# canDrive_hw_board2_v2.net
KiCad netlist of a schematic drawn in Altium Designer
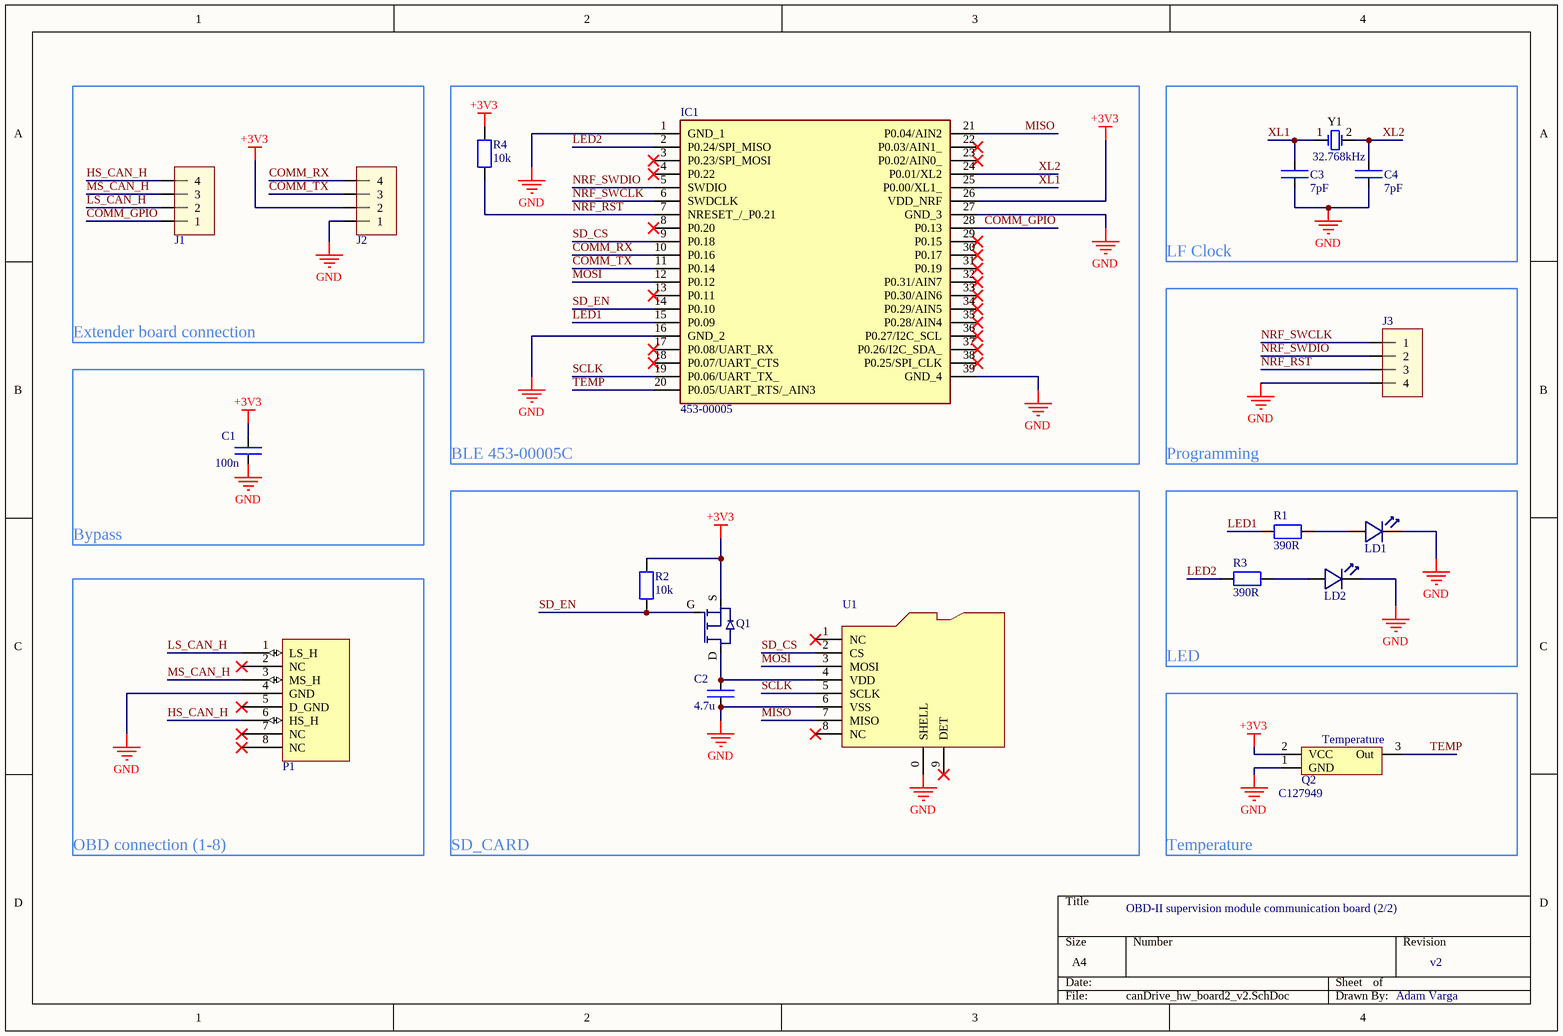
[diagram p0: canDrive_hw_board2_v2.SchDoc]

(export (version "E")
  (design (tool "Eeschema 10.0.6"))
  (components
    (comp (ref "C1")
      (value "100n")
      (footprint "C0603")
      (description "Capacitor")
      (libsource (lib "canDrive_comp_sch_lib") (part "Capacitor"))
    )
    (comp (ref "C2")
      (value "4.7u")
      (footprint "C0603")
      (description "Capacitor")
      (libsource (lib "canDrive_comp_sch_lib") (part "Capacitor"))
    )
    (comp (ref "C3")
      (value "7pF")
      (footprint "C0603")
      (description "Capacitor")
      (fields (field (name "PART") "C326971"))
      (libsource (lib "canDrive_comp_sch_lib") (part "Capacitor"))
    )
    (comp (ref "C4")
      (value "7pF")
      (footprint "C0603")
      (description "Capacitor")
      (fields (field (name "PART") "C326971"))
      (libsource (lib "canDrive_comp_sch_lib") (part "Capacitor"))
    )
    (comp (ref "IC1")
      (value "453-00005")
      (footprint "45300005")
      (description "Integrated Circuit")
      (libsource (lib "canDrive_comp_sch_lib") (part "453-00005"))
    )
    (comp (ref "J1")
      (value "CON_1x4")
      (footprint "127mm_header_4pin")
      (description "1x4 connector")
      (libsource (lib "canDrive_comp_sch_lib") (part "CON_1x4"))
    )
    (comp (ref "J2")
      (value "CON_1x4")
      (footprint "127mm_header_4pin")
      (description "1x4 connector")
      (libsource (lib "canDrive_comp_sch_lib") (part "CON_1x4"))
    )
    (comp (ref "J3")
      (value "CON_1x4")
      (footprint "ribbon4pin")
      (description "1x4 connector")
      (libsource (lib "") (part "CON_1x4_1"))
    )
    (comp (ref "LD1")
      (value "LED")
      (footprint "LED_0603")
      (libsource (lib "canDrive_comp_sch_lib") (part "LED"))
    )
    (comp (ref "LD2")
      (value "LED")
      (footprint "LED_0603")
      (libsource (lib "canDrive_comp_sch_lib") (part "LED"))
    )
    (comp (ref "P1")
      (value "OBD_connector1-8")
      (footprint "OBD1-8")
      (libsource (lib "canDrive_comp_sch_lib") (part "OBD1-8"))
    )
    (comp (ref "Q1")
      (value "MOFFET_pCH")
      (footprint "SOT-23")
      (description "MOSFET P_CH")
      (fields (field (name "PART") "C130884"))
      (libsource (lib "canDrive_comp_sch_lib") (part "MOFFET_pCH"))
    )
    (comp (ref "Q2")
      (value "Temp_sensor")
      (footprint "SOT-23")
      (description "Temperature sensor")
      (fields (field (name "PART") "C127949"))
      (libsource (lib "canDrive_comp_sch_lib") (part "Temp_sensor"))
    )
    (comp (ref "R1")
      (value "390R")
      (footprint "R0603")
      (description "Resistor")
      (libsource (lib "canDrive_comp_sch_lib") (part "Resistor"))
    )
    (comp (ref "R2")
      (value "10k")
      (footprint "R0603")
      (description "Resistor")
      (libsource (lib "canDrive_comp_sch_lib") (part "Resistor"))
    )
    (comp (ref "R3")
      (value "390R")
      (footprint "R0603")
      (description "Resistor")
      (libsource (lib "canDrive_comp_sch_lib") (part "Resistor"))
    )
    (comp (ref "R4")
      (value "10k")
      (footprint "R0603")
      (description "Resistor")
      (libsource (lib "canDrive_comp_sch_lib") (part "Resistor"))
    )
    (comp (ref "U1")
      (value "MicroSD Molex 105162-0001")
      (footprint "MICRO_USB_BIG")
      (fields (field (name "PART") "C266612"))
      (libsource (lib "canDrive_comp_sch_lib") (part "MicroSD Molex 105162-0001"))
    )
    (comp (ref "Y1")
      (value "32.768kHz")
      (footprint "TXC-9HT10_V")
      (description "Tuning Fork, 32.768 KHz, -40 to 85 degC, 2-Pin SMD, RoHS, Tape and Reel")
      (fields (field (name "PART") "C280830") (field (name "Comment") "9HT10-32.768KDZF-T"))
      (libsource (lib "canDrive_comp_sch_lib") (part "9HT10-32.768KDZF-T"))
    )
  )
  (nets
    (net (code "1") (name "+3V3") (class "Default")
      (node (ref "C1") (pin "1") (pinfunction "1_1") (pintype "passive"))
      (node (ref "IC1") (pin "26") (pinfunction "VDD_NRF_26") (pintype "passive"))
      (node (ref "J2") (pin "2") (pinfunction "2_2") (pintype "passive"))
      (node (ref "Q1") (pin "S") (pinfunction "S_S") (pintype "passive"))
      (node (ref "Q2") (pin "2") (pinfunction "VCC_2") (pintype "passive"))
      (node (ref "R2") (pin "1") (pinfunction "1_1") (pintype "passive"))
      (node (ref "R4") (pin "1") (pinfunction "1_1") (pintype "passive"))
    )
    (net (code "2") (name "/COMM_GPIO") (class "Default")
      (node (ref "IC1") (pin "28") (pinfunction "P0.13_28") (pintype "passive"))
      (node (ref "J1") (pin "1") (pinfunction "1_1") (pintype "passive"))
    )
    (net (code "3") (name "/COMM_RX") (class "Default")
      (node (ref "IC1") (pin "10") (pinfunction "P0.16_10") (pintype "passive"))
      (node (ref "J2") (pin "4") (pinfunction "4_4") (pintype "passive"))
    )
    (net (code "4") (name "/COMM_TX") (class "Default")
      (node (ref "IC1") (pin "11") (pinfunction "P0.14_11") (pintype "passive"))
      (node (ref "J2") (pin "3") (pinfunction "3_3") (pintype "passive"))
    )
    (net (code "5") (name "/HS_CAN_H") (class "Default")
      (node (ref "J1") (pin "4") (pinfunction "4_4") (pintype "passive"))
      (node (ref "P1") (pin "6") (pinfunction "HS_H_6") (pintype "bidirectional"))
    )
    (net (code "6") (name "/LED1") (class "Default")
      (node (ref "IC1") (pin "15") (pinfunction "P0.09_15") (pintype "passive"))
      (node (ref "R1") (pin "1") (pinfunction "1_1") (pintype "passive"))
    )
    (net (code "7") (name "/LED2") (class "Default")
      (node (ref "IC1") (pin "2") (pinfunction "P0.24/SPI_MISO_2") (pintype "passive"))
      (node (ref "R3") (pin "1") (pinfunction "1_1") (pintype "passive"))
    )
    (net (code "8") (name "/LS_CAN_H") (class "Default")
      (node (ref "J1") (pin "2") (pinfunction "2_2") (pintype "passive"))
      (node (ref "P1") (pin "1") (pinfunction "LS_H_1") (pintype "bidirectional"))
    )
    (net (code "9") (name "/MISO") (class "Default")
      (node (ref "IC1") (pin "21") (pinfunction "P0.04/AIN2_21") (pintype "passive"))
      (node (ref "U1") (pin "7") (pinfunction "MISO_7") (pintype "passive"))
    )
    (net (code "10") (name "/MOSI") (class "Default")
      (node (ref "IC1") (pin "12") (pinfunction "P0.12_12") (pintype "passive"))
      (node (ref "U1") (pin "3") (pinfunction "MOSI_3") (pintype "passive"))
    )
    (net (code "11") (name "/MS_CAN_H") (class "Default")
      (node (ref "J1") (pin "3") (pinfunction "3_3") (pintype "passive"))
      (node (ref "P1") (pin "3") (pinfunction "MS_H_3") (pintype "bidirectional"))
    )
    (net (code "12") (name "/NRF_RST") (class "Default")
      (node (ref "IC1") (pin "7") (pinfunction "NRESET_/_P0.21_7") (pintype "passive"))
      (node (ref "J3") (pin "3") (pinfunction "3_3") (pintype "passive"))
      (node (ref "R4") (pin "0") (pinfunction "0_0") (pintype "passive"))
    )
    (net (code "13") (name "/NRF_SWCLK") (class "Default")
      (node (ref "IC1") (pin "6") (pinfunction "SWDCLK_6") (pintype "passive"))
      (node (ref "J3") (pin "1") (pinfunction "1_1") (pintype "passive"))
    )
    (net (code "14") (name "/NRF_SWDIO") (class "Default")
      (node (ref "IC1") (pin "5") (pinfunction "SWDIO_5") (pintype "passive"))
      (node (ref "J3") (pin "2") (pinfunction "2_2") (pintype "passive"))
    )
    (net (code "15") (name "/SCLK") (class "Default")
      (node (ref "IC1") (pin "19") (pinfunction "P0.06/UART_TX__19") (pintype "passive"))
      (node (ref "U1") (pin "5") (pinfunction "SCLK_5") (pintype "passive"))
    )
    (net (code "16") (name "/SD_CS") (class "Default")
      (node (ref "IC1") (pin "9") (pinfunction "P0.18_9") (pintype "passive"))
      (node (ref "U1") (pin "2") (pinfunction "CS_2") (pintype "passive"))
    )
    (net (code "17") (name "/SD_EN") (class "Default")
      (node (ref "IC1") (pin "14") (pinfunction "P0.10_14") (pintype "passive"))
      (node (ref "Q1") (pin "G") (pinfunction "G_G") (pintype "passive"))
      (node (ref "R2") (pin "0") (pinfunction "0_0") (pintype "passive"))
    )
    (net (code "18") (name "/TEMP") (class "Default")
      (node (ref "IC1") (pin "20") (pinfunction "P0.05/UART_RTS/_AIN3_20") (pintype "passive"))
      (node (ref "Q2") (pin "3") (pinfunction "Out_3") (pintype "passive"))
    )
    (net (code "19") (name "/XL1") (class "Default")
      (node (ref "C3") (pin "1") (pinfunction "1_1") (pintype "passive"))
      (node (ref "IC1") (pin "25") (pinfunction "P0.00/XL1__25") (pintype "passive"))
      (node (ref "Y1") (pin "1") (pinfunction "1_1") (pintype "passive"))
    )
    (net (code "20") (name "/XL2") (class "Default")
      (node (ref "C4") (pin "1") (pinfunction "1_1") (pintype "passive"))
      (node (ref "IC1") (pin "24") (pinfunction "P0.01/XL2_24") (pintype "passive"))
      (node (ref "Y1") (pin "2") (pinfunction "2_2") (pintype "passive"))
    )
    (net (code "21") (name "GND") (class "Default")
      (node (ref "C1") (pin "0") (pinfunction "0_0") (pintype "passive"))
      (node (ref "C2") (pin "0") (pinfunction "0_0") (pintype "passive"))
      (node (ref "C3") (pin "0") (pinfunction "0_0") (pintype "passive"))
      (node (ref "C4") (pin "0") (pinfunction "0_0") (pintype "passive"))
      (node (ref "IC1") (pin "1") (pinfunction "GND_1_1") (pintype "passive"))
      (node (ref "IC1") (pin "16") (pinfunction "GND_2_16") (pintype "passive"))
      (node (ref "IC1") (pin "27") (pinfunction "GND_3_27") (pintype "passive"))
      (node (ref "IC1") (pin "39") (pinfunction "GND_4_39") (pintype "passive"))
      (node (ref "J2") (pin "1") (pinfunction "1_1") (pintype "passive"))
      (node (ref "J3") (pin "4") (pinfunction "4_4") (pintype "passive"))
      (node (ref "LD1") (pin "C") (pinfunction "C_C") (pintype "passive"))
      (node (ref "LD2") (pin "C") (pinfunction "C_C") (pintype "passive"))
      (node (ref "P1") (pin "4") (pinfunction "GND_4") (pintype "power_in"))
      (node (ref "Q2") (pin "1") (pinfunction "GND_1") (pintype "passive"))
      (node (ref "U1") (pin "0") (pinfunction "SHELL_0") (pintype "passive"))
      (node (ref "U1") (pin "6") (pinfunction "VSS_6") (pintype "passive"))
    )
    (net (code "22") (name "Net-(LD1-PadA)") (class "Default")
      (node (ref "LD1") (pin "A") (pinfunction "A_A") (pintype "passive"))
      (node (ref "R1") (pin "0") (pinfunction "0_0") (pintype "passive"))
    )
    (net (code "23") (name "Net-(LD2-PadA)") (class "Default")
      (node (ref "LD2") (pin "A") (pinfunction "A_A") (pintype "passive"))
      (node (ref "R3") (pin "0") (pinfunction "0_0") (pintype "passive"))
    )
    (net (code "24") (name "Net-(U1-VDD)") (class "Default")
      (node (ref "C2") (pin "1") (pinfunction "1_1") (pintype "passive"))
      (node (ref "Q1") (pin "D") (pinfunction "D_D") (pintype "passive"))
      (node (ref "U1") (pin "4") (pinfunction "VDD_4") (pintype "passive"))
    )
    (net (code "25") (name "unconnected-(IC1-P0.02{slash}AIN0_-Pad23)") (class "Default")
      (node (ref "IC1") (pin "23") (pinfunction "P0.02/AIN0__23") (pintype "passive+no_connect"))
    )
    (net (code "26") (name "unconnected-(IC1-P0.03{slash}AIN1_-Pad22)") (class "Default")
      (node (ref "IC1") (pin "22") (pinfunction "P0.03/AIN1__22") (pintype "passive+no_connect"))
    )
    (net (code "27") (name "unconnected-(IC1-P0.07{slash}UART_CTS-Pad18)") (class "Default")
      (node (ref "IC1") (pin "18") (pinfunction "P0.07/UART_CTS_18") (pintype "passive+no_connect"))
    )
    (net (code "28") (name "unconnected-(IC1-P0.08{slash}UART_RX-Pad17)") (class "Default")
      (node (ref "IC1") (pin "17") (pinfunction "P0.08/UART_RX_17") (pintype "passive+no_connect"))
    )
    (net (code "29") (name "unconnected-(IC1-P0.11-Pad13)") (class "Default")
      (node (ref "IC1") (pin "13") (pinfunction "P0.11_13") (pintype "passive+no_connect"))
    )
    (net (code "30") (name "unconnected-(IC1-P0.15-Pad29)") (class "Default")
      (node (ref "IC1") (pin "29") (pinfunction "P0.15_29") (pintype "passive+no_connect"))
    )
    (net (code "31") (name "unconnected-(IC1-P0.17-Pad30)") (class "Default")
      (node (ref "IC1") (pin "30") (pinfunction "P0.17_30") (pintype "passive+no_connect"))
    )
    (net (code "32") (name "unconnected-(IC1-P0.19-Pad31)") (class "Default")
      (node (ref "IC1") (pin "31") (pinfunction "P0.19_31") (pintype "passive+no_connect"))
    )
    (net (code "33") (name "unconnected-(IC1-P0.20-Pad8)") (class "Default")
      (node (ref "IC1") (pin "8") (pinfunction "P0.20_8") (pintype "passive+no_connect"))
    )
    (net (code "34") (name "unconnected-(IC1-P0.22-Pad4)") (class "Default")
      (node (ref "IC1") (pin "4") (pinfunction "P0.22_4") (pintype "passive+no_connect"))
    )
    (net (code "35") (name "unconnected-(IC1-P0.23{slash}SPI_MOSI-Pad3)") (class "Default")
      (node (ref "IC1") (pin "3") (pinfunction "P0.23/SPI_MOSI_3") (pintype "passive+no_connect"))
    )
    (net (code "36") (name "unconnected-(IC1-P0.25{slash}SPI_CLK-Pad38)") (class "Default")
      (node (ref "IC1") (pin "38") (pinfunction "P0.25/SPI_CLK_38") (pintype "passive+no_connect"))
    )
    (net (code "37") (name "unconnected-(IC1-P0.26{slash}I2C_SDA_-Pad37)") (class "Default")
      (node (ref "IC1") (pin "37") (pinfunction "P0.26/I2C_SDA__37") (pintype "passive+no_connect"))
    )
    (net (code "38") (name "unconnected-(IC1-P0.27{slash}I2C_SCL-Pad36)") (class "Default")
      (node (ref "IC1") (pin "36") (pinfunction "P0.27/I2C_SCL_36") (pintype "passive+no_connect"))
    )
    (net (code "39") (name "unconnected-(IC1-P0.28{slash}AIN4-Pad35)") (class "Default")
      (node (ref "IC1") (pin "35") (pinfunction "P0.28/AIN4_35") (pintype "passive+no_connect"))
    )
    (net (code "40") (name "unconnected-(IC1-P0.29{slash}AIN5-Pad34)") (class "Default")
      (node (ref "IC1") (pin "34") (pinfunction "P0.29/AIN5_34") (pintype "passive+no_connect"))
    )
    (net (code "41") (name "unconnected-(IC1-P0.30{slash}AIN6-Pad33)") (class "Default")
      (node (ref "IC1") (pin "33") (pinfunction "P0.30/AIN6_33") (pintype "passive+no_connect"))
    )
    (net (code "42") (name "unconnected-(IC1-P0.31{slash}AIN7-Pad32)") (class "Default")
      (node (ref "IC1") (pin "32") (pinfunction "P0.31/AIN7_32") (pintype "passive+no_connect"))
    )
    (net (code "43") (name "unconnected-(P1-D_GND-Pad5)") (class "Default")
      (node (ref "P1") (pin "5") (pinfunction "D_GND_5") (pintype "power_in+no_connect"))
    )
    (net (code "44") (name "unconnected-(P1-NC-Pad2)") (class "Default")
      (node (ref "P1") (pin "2") (pinfunction "NC_2") (pintype "passive+no_connect"))
    )
    (net (code "45") (name "unconnected-(P1-NC-Pad7)") (class "Default")
      (node (ref "P1") (pin "7") (pinfunction "NC_7") (pintype "passive+no_connect"))
    )
    (net (code "46") (name "unconnected-(P1-NC-Pad8)") (class "Default")
      (node (ref "P1") (pin "8") (pinfunction "NC_8") (pintype "passive+no_connect"))
    )
    (net (code "47") (name "unconnected-(U1-DET-Pad9)") (class "Default")
      (node (ref "U1") (pin "9") (pinfunction "DET_9") (pintype "passive+no_connect"))
    )
    (net (code "48") (name "unconnected-(U1-NC-Pad1)") (class "Default")
      (node (ref "U1") (pin "1") (pinfunction "NC_1") (pintype "passive+no_connect"))
    )
    (net (code "49") (name "unconnected-(U1-NC-Pad8)") (class "Default")
      (node (ref "U1") (pin "8") (pinfunction "NC_8") (pintype "passive+no_connect"))
    )
  )
)
